# pwm_outputs.net
KiCad netlist of a schematic drawn in Altium Designer
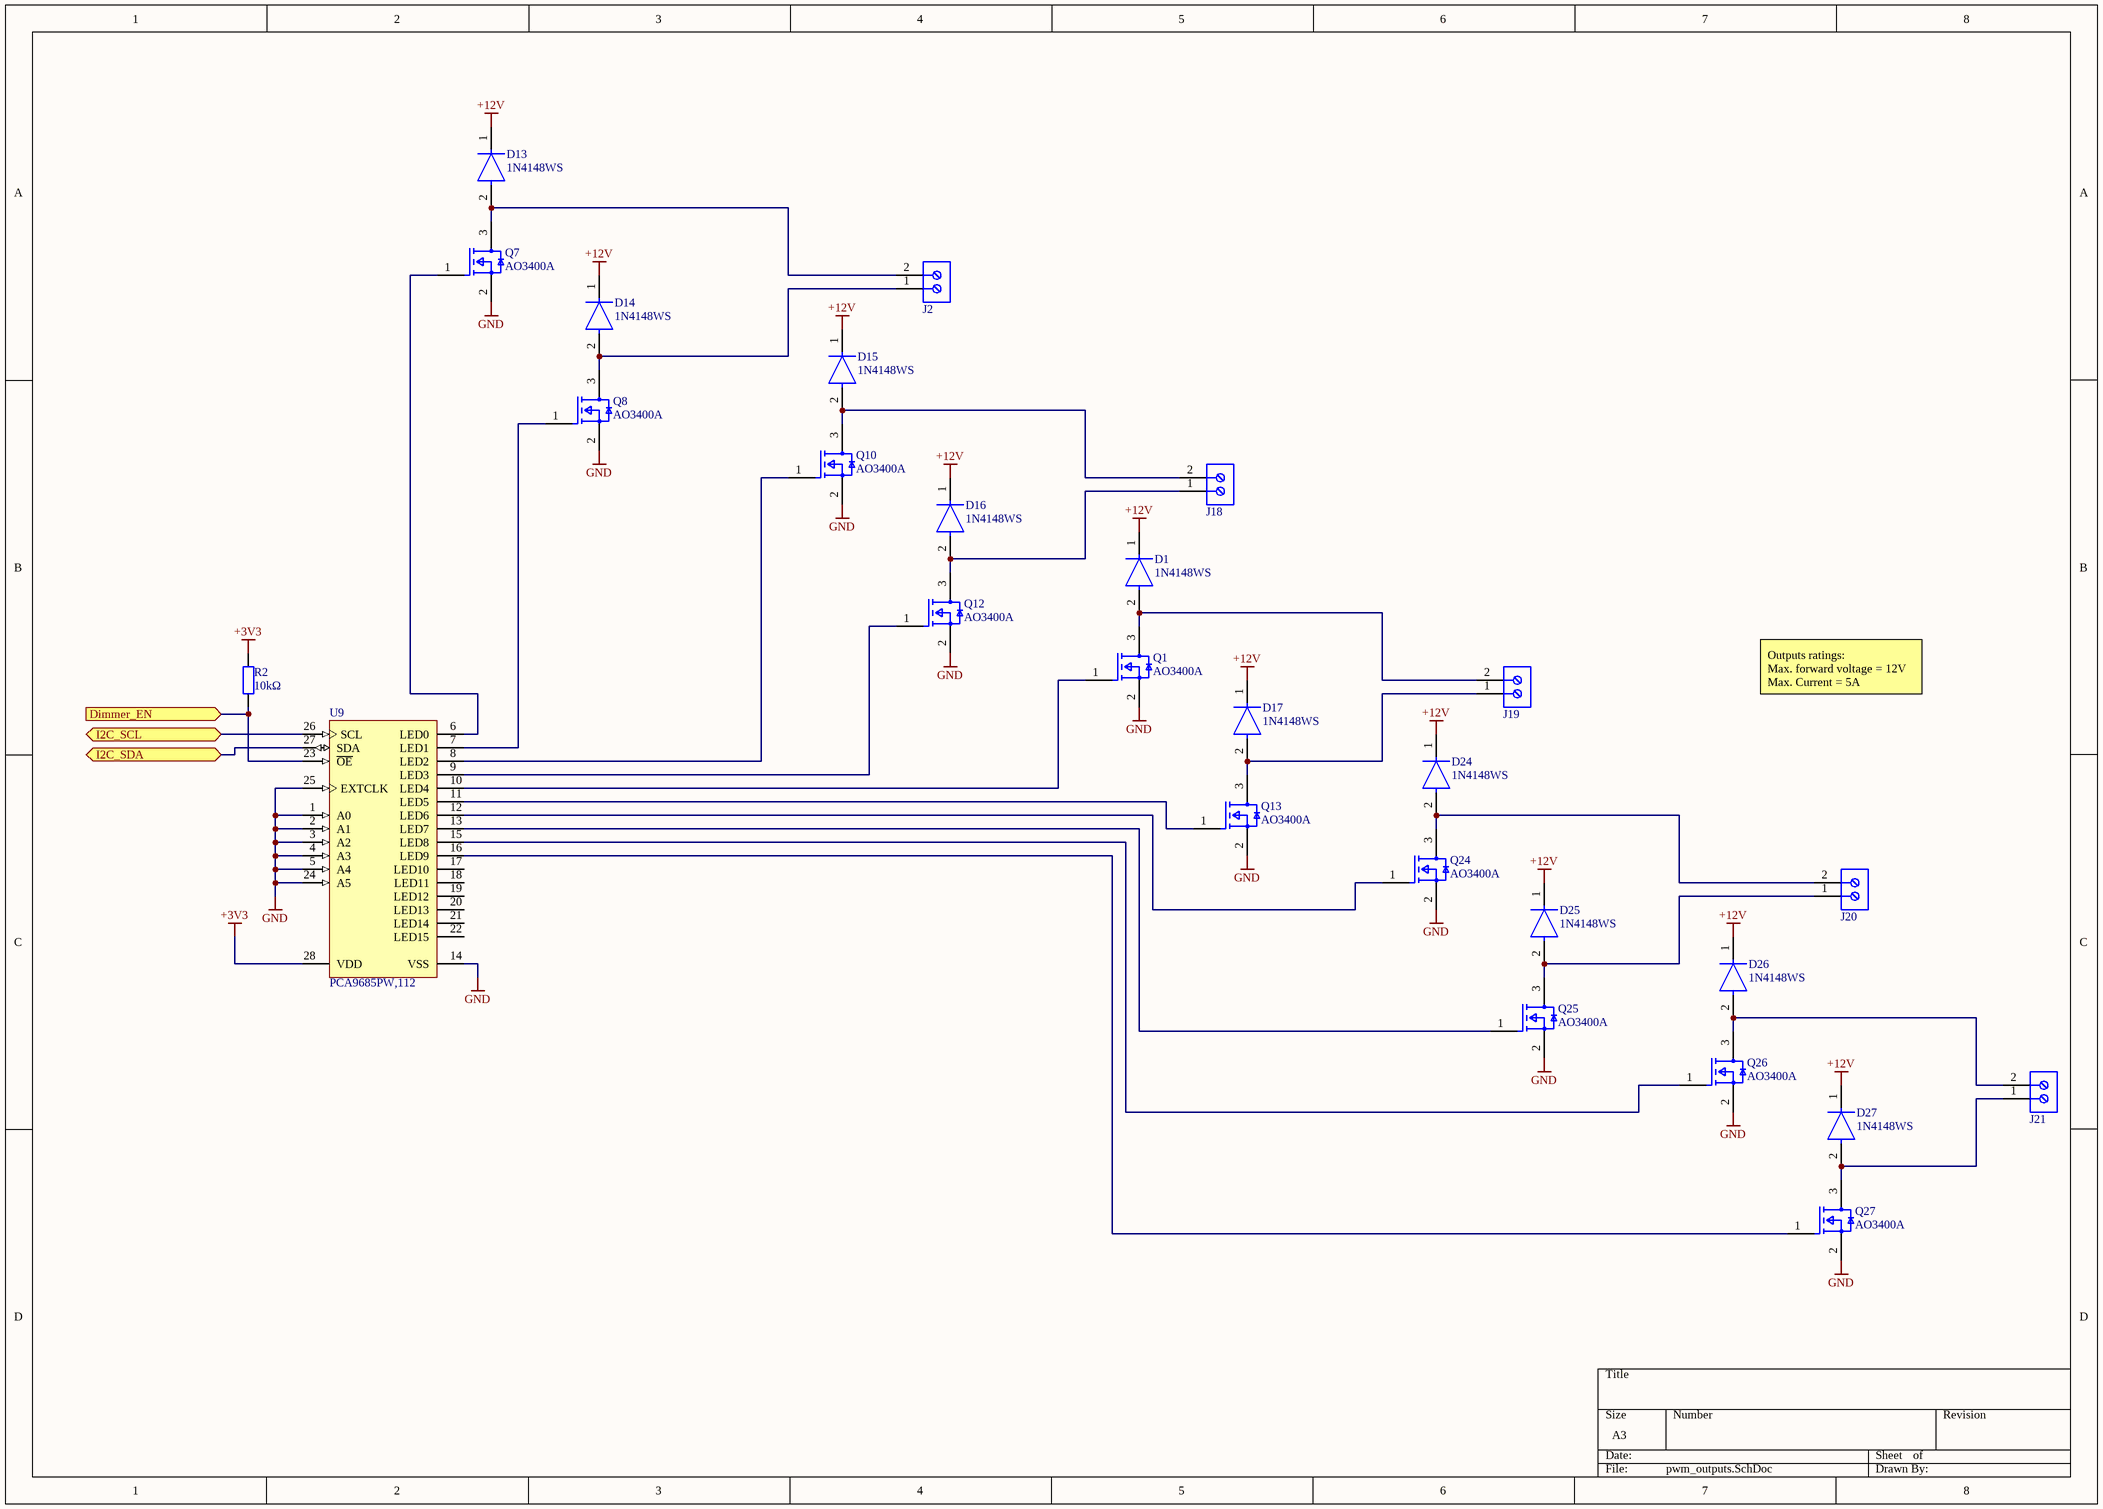
[diagram p0: pwm_outputs.SchDoc]

(export (version "E")
  (design (tool "Eeschema 10.0.6"))
  (components
    (comp (ref "D1")
      (value "1N4148WS")
      (footprint "FP-477AB-IPC_C")
      (description "DIODE GEN PURP 75V 150MA SOD323F")
      (libsource (lib "Altium Content Vault") (part "d7152d700b627762746794eb795d46e"))
    )
    (comp (ref "D13")
      (value "1N4148WS")
      (footprint "FP-477AB-IPC_C")
      (description "DIODE GEN PURP 75V 150MA SOD323F")
      (libsource (lib "Altium Content Vault") (part "d7152d700b627762746794eb795d46e"))
    )
    (comp (ref "D14")
      (value "1N4148WS")
      (footprint "FP-477AB-IPC_C")
      (description "DIODE GEN PURP 75V 150MA SOD323F")
      (libsource (lib "Altium Content Vault") (part "d7152d700b627762746794eb795d46e"))
    )
    (comp (ref "D15")
      (value "1N4148WS")
      (footprint "FP-477AB-IPC_C")
      (description "DIODE GEN PURP 75V 150MA SOD323F")
      (libsource (lib "Altium Content Vault") (part "d7152d700b627762746794eb795d46e"))
    )
    (comp (ref "D16")
      (value "1N4148WS")
      (footprint "FP-477AB-IPC_C")
      (description "DIODE GEN PURP 75V 150MA SOD323F")
      (libsource (lib "Altium Content Vault") (part "d7152d700b627762746794eb795d46e"))
    )
    (comp (ref "D17")
      (value "1N4148WS")
      (footprint "FP-477AB-IPC_C")
      (description "DIODE GEN PURP 75V 150MA SOD323F")
      (libsource (lib "Altium Content Vault") (part "d7152d700b627762746794eb795d46e"))
    )
    (comp (ref "D24")
      (value "1N4148WS")
      (footprint "FP-477AB-IPC_C")
      (description "DIODE GEN PURP 75V 150MA SOD323F")
      (libsource (lib "Altium Content Vault") (part "d7152d700b627762746794eb795d46e"))
    )
    (comp (ref "D25")
      (value "1N4148WS")
      (footprint "FP-477AB-IPC_C")
      (description "DIODE GEN PURP 75V 150MA SOD323F")
      (libsource (lib "Altium Content Vault") (part "d7152d700b627762746794eb795d46e"))
    )
    (comp (ref "D26")
      (value "1N4148WS")
      (footprint "FP-477AB-IPC_C")
      (description "DIODE GEN PURP 75V 150MA SOD323F")
      (libsource (lib "Altium Content Vault") (part "d7152d700b627762746794eb795d46e"))
    )
    (comp (ref "D27")
      (value "1N4148WS")
      (footprint "FP-477AB-IPC_C")
      (description "DIODE GEN PURP 75V 150MA SOD323F")
      (libsource (lib "Altium Content Vault") (part "d7152d700b627762746794eb795d46e"))
    )
    (comp (ref "J2")
      (value "282836-2")
      (footprint "TECO-282836-2_V")
      (description "Female Header, Pitch 5 mm, 1 x 2 Position, Height 10 mm, Tail Length 3.5 mm, Rohs, Bulk")
      (fields (field (name "VOLTAGE") "300V") (field (name "MANUFACTURER") "TE Connectivity"))
      (libsource (lib "Altium Content Vault") (part "CN-1P-F-TB2"))
    )
    (comp (ref "J18")
      (value "282836-2")
      (footprint "TECO-282836-2_V")
      (description "Female Header, Pitch 5 mm, 1 x 2 Position, Height 10 mm, Tail Length 3.5 mm, Rohs, Bulk")
      (fields (field (name "VOLTAGE") "300V") (field (name "MANUFACTURER") "TE Connectivity"))
      (libsource (lib "Altium Content Vault") (part "CN-1P-F-TB2"))
    )
    (comp (ref "J19")
      (value "282836-2")
      (footprint "TECO-282836-2_V")
      (description "Female Header, Pitch 5 mm, 1 x 2 Position, Height 10 mm, Tail Length 3.5 mm, Rohs, Bulk")
      (fields (field (name "VOLTAGE") "300V") (field (name "MANUFACTURER") "TE Connectivity"))
      (libsource (lib "Altium Content Vault") (part "CN-1P-F-TB2"))
    )
    (comp (ref "J20")
      (value "282836-2")
      (footprint "TECO-282836-2_V")
      (description "Female Header, Pitch 5 mm, 1 x 2 Position, Height 10 mm, Tail Length 3.5 mm, Rohs, Bulk")
      (fields (field (name "VOLTAGE") "300V") (field (name "MANUFACTURER") "TE Connectivity"))
      (libsource (lib "Altium Content Vault") (part "CN-1P-F-TB2"))
    )
    (comp (ref "J21")
      (value "282836-2")
      (footprint "TECO-282836-2_V")
      (description "Female Header, Pitch 5 mm, 1 x 2 Position, Height 10 mm, Tail Length 3.5 mm, Rohs, Bulk")
      (fields (field (name "VOLTAGE") "300V") (field (name "MANUFACTURER") "TE Connectivity"))
      (libsource (lib "Altium Content Vault") (part "CN-1P-F-TB2"))
    )
    (comp (ref "Q1")
      (value "AO3400A")
      (footprint "SOT-23")
      (description "MOSFET N-CH 30V 5.7A SOT23")
      (libsource (lib "integrated_library") (part "MOSFET_AO3400A"))
    )
    (comp (ref "Q7")
      (value "AO3400A")
      (footprint "SOT-23")
      (description "MOSFET N-CH 30V 5.7A SOT23")
      (libsource (lib "integrated_library") (part "MOSFET_AO3400A"))
    )
    (comp (ref "Q8")
      (value "AO3400A")
      (footprint "SOT-23")
      (description "MOSFET N-CH 30V 5.7A SOT23")
      (libsource (lib "integrated_library") (part "MOSFET_AO3400A"))
    )
    (comp (ref "Q10")
      (value "AO3400A")
      (footprint "SOT-23")
      (description "MOSFET N-CH 30V 5.7A SOT23")
      (libsource (lib "integrated_library") (part "MOSFET_AO3400A"))
    )
    (comp (ref "Q12")
      (value "AO3400A")
      (footprint "SOT-23")
      (description "MOSFET N-CH 30V 5.7A SOT23")
      (libsource (lib "integrated_library") (part "MOSFET_AO3400A"))
    )
    (comp (ref "Q13")
      (value "AO3400A")
      (footprint "SOT-23")
      (description "MOSFET N-CH 30V 5.7A SOT23")
      (libsource (lib "integrated_library") (part "MOSFET_AO3400A"))
    )
    (comp (ref "Q24")
      (value "AO3400A")
      (footprint "SOT-23")
      (description "MOSFET N-CH 30V 5.7A SOT23")
      (libsource (lib "integrated_library") (part "MOSFET_AO3400A"))
    )
    (comp (ref "Q25")
      (value "AO3400A")
      (footprint "SOT-23")
      (description "MOSFET N-CH 30V 5.7A SOT23")
      (libsource (lib "integrated_library") (part "MOSFET_AO3400A"))
    )
    (comp (ref "Q26")
      (value "AO3400A")
      (footprint "SOT-23")
      (description "MOSFET N-CH 30V 5.7A SOT23")
      (libsource (lib "integrated_library") (part "MOSFET_AO3400A"))
    )
    (comp (ref "Q27")
      (value "AO3400A")
      (footprint "SOT-23")
      (description "MOSFET N-CH 30V 5.7A SOT23")
      (libsource (lib "integrated_library") (part "MOSFET_AO3400A"))
    )
    (comp (ref "R2")
      (value "10kΩ")
      (footprint "RESC2013X50X30ML20T20")
      (description "Resistor")
      (libsource (lib "PCB_Project") (part "Res_0805"))
    )
    (comp (ref "U9")
      (value "PCA9685PW,112")
      (footprint "SOT361-1_V")
      (fields (field (name "PARTNUMBER") "PCA9685"))
      (libsource (lib "Altium Content Vault") (part "NXP-PCA9685-SOT361-1"))
    )
  )
  (nets
    (net (code "1") (name "+3V3") (class "Default")
      (node (ref "R2") (pin "2") (pinfunction "2_2") (pintype "passive"))
      (node (ref "U9") (pin "28") (pinfunction "VDD_28") (pintype "power_in"))
    )
    (net (code "2") (name "+12V") (class "Default")
      (node (ref "D1") (pin "1") (pinfunction "C_1") (pintype "passive"))
      (node (ref "D13") (pin "1") (pinfunction "C_1") (pintype "passive"))
      (node (ref "D14") (pin "1") (pinfunction "C_1") (pintype "passive"))
      (node (ref "D15") (pin "1") (pinfunction "C_1") (pintype "passive"))
      (node (ref "D16") (pin "1") (pinfunction "C_1") (pintype "passive"))
      (node (ref "D17") (pin "1") (pinfunction "C_1") (pintype "passive"))
      (node (ref "D24") (pin "1") (pinfunction "C_1") (pintype "passive"))
      (node (ref "D25") (pin "1") (pinfunction "C_1") (pintype "passive"))
      (node (ref "D26") (pin "1") (pinfunction "C_1") (pintype "passive"))
      (node (ref "D27") (pin "1") (pinfunction "C_1") (pintype "passive"))
    )
    (net (code "3") (name "/Dimmer_EN") (class "Default")
      (node (ref "R2") (pin "1") (pinfunction "1_1") (pintype "passive"))
      (node (ref "U9") (pin "23") (pinfunction "~{OE}_23") (pintype "input"))
    )
    (net (code "4") (name "/I2C_SCL") (class "Default")
      (node (ref "U9") (pin "26") (pinfunction "SCL_26") (pintype "input"))
    )
    (net (code "5") (name "/I2C_SDA") (class "Default")
      (node (ref "U9") (pin "27") (pinfunction "SDA_27") (pintype "bidirectional"))
    )
    (net (code "6") (name "GND") (class "Default")
      (node (ref "Q1") (pin "2") (pinfunction "S_2") (pintype "passive"))
      (node (ref "Q10") (pin "2") (pinfunction "S_2") (pintype "passive"))
      (node (ref "Q12") (pin "2") (pinfunction "S_2") (pintype "passive"))
      (node (ref "Q13") (pin "2") (pinfunction "S_2") (pintype "passive"))
      (node (ref "Q24") (pin "2") (pinfunction "S_2") (pintype "passive"))
      (node (ref "Q25") (pin "2") (pinfunction "S_2") (pintype "passive"))
      (node (ref "Q26") (pin "2") (pinfunction "S_2") (pintype "passive"))
      (node (ref "Q27") (pin "2") (pinfunction "S_2") (pintype "passive"))
      (node (ref "Q7") (pin "2") (pinfunction "S_2") (pintype "passive"))
      (node (ref "Q8") (pin "2") (pinfunction "S_2") (pintype "passive"))
      (node (ref "U9") (pin "1") (pinfunction "A0_1") (pintype "input"))
      (node (ref "U9") (pin "14") (pinfunction "VSS_14") (pintype "power_in"))
      (node (ref "U9") (pin "2") (pinfunction "A1_2") (pintype "input"))
      (node (ref "U9") (pin "24") (pinfunction "A5_24") (pintype "input"))
      (node (ref "U9") (pin "25") (pinfunction "EXTCLK_25") (pintype "input"))
      (node (ref "U9") (pin "3") (pinfunction "A2_3") (pintype "input"))
      (node (ref "U9") (pin "4") (pinfunction "A3_4") (pintype "input"))
      (node (ref "U9") (pin "5") (pinfunction "A4_5") (pintype "input"))
    )
    (net (code "7") (name "Net-(D1-A)") (class "Default")
      (node (ref "D1") (pin "2") (pinfunction "A_2") (pintype "passive"))
      (node (ref "J19") (pin "2") (pinfunction "2_2") (pintype "passive"))
      (node (ref "Q1") (pin "3") (pinfunction "D_3") (pintype "passive"))
    )
    (net (code "8") (name "Net-(D13-A)") (class "Default")
      (node (ref "D13") (pin "2") (pinfunction "A_2") (pintype "passive"))
      (node (ref "J2") (pin "2") (pinfunction "2_2") (pintype "passive"))
      (node (ref "Q7") (pin "3") (pinfunction "D_3") (pintype "passive"))
    )
    (net (code "9") (name "Net-(D14-A)") (class "Default")
      (node (ref "D14") (pin "2") (pinfunction "A_2") (pintype "passive"))
      (node (ref "J2") (pin "1") (pinfunction "1_1") (pintype "passive"))
      (node (ref "Q8") (pin "3") (pinfunction "D_3") (pintype "passive"))
    )
    (net (code "10") (name "Net-(D15-A)") (class "Default")
      (node (ref "D15") (pin "2") (pinfunction "A_2") (pintype "passive"))
      (node (ref "J18") (pin "2") (pinfunction "2_2") (pintype "passive"))
      (node (ref "Q10") (pin "3") (pinfunction "D_3") (pintype "passive"))
    )
    (net (code "11") (name "Net-(D16-A)") (class "Default")
      (node (ref "D16") (pin "2") (pinfunction "A_2") (pintype "passive"))
      (node (ref "J18") (pin "1") (pinfunction "1_1") (pintype "passive"))
      (node (ref "Q12") (pin "3") (pinfunction "D_3") (pintype "passive"))
    )
    (net (code "12") (name "Net-(D17-A)") (class "Default")
      (node (ref "D17") (pin "2") (pinfunction "A_2") (pintype "passive"))
      (node (ref "J19") (pin "1") (pinfunction "1_1") (pintype "passive"))
      (node (ref "Q13") (pin "3") (pinfunction "D_3") (pintype "passive"))
    )
    (net (code "13") (name "Net-(D24-A)") (class "Default")
      (node (ref "D24") (pin "2") (pinfunction "A_2") (pintype "passive"))
      (node (ref "J20") (pin "2") (pinfunction "2_2") (pintype "passive"))
      (node (ref "Q24") (pin "3") (pinfunction "D_3") (pintype "passive"))
    )
    (net (code "14") (name "Net-(D25-A)") (class "Default")
      (node (ref "D25") (pin "2") (pinfunction "A_2") (pintype "passive"))
      (node (ref "J20") (pin "1") (pinfunction "1_1") (pintype "passive"))
      (node (ref "Q25") (pin "3") (pinfunction "D_3") (pintype "passive"))
    )
    (net (code "15") (name "Net-(D26-A)") (class "Default")
      (node (ref "D26") (pin "2") (pinfunction "A_2") (pintype "passive"))
      (node (ref "J21") (pin "2") (pinfunction "2_2") (pintype "passive"))
      (node (ref "Q26") (pin "3") (pinfunction "D_3") (pintype "passive"))
    )
    (net (code "16") (name "Net-(D27-A)") (class "Default")
      (node (ref "D27") (pin "2") (pinfunction "A_2") (pintype "passive"))
      (node (ref "J21") (pin "1") (pinfunction "1_1") (pintype "passive"))
      (node (ref "Q27") (pin "3") (pinfunction "D_3") (pintype "passive"))
    )
    (net (code "17") (name "Net-(Q1-G)") (class "Default")
      (node (ref "Q1") (pin "1") (pinfunction "G_1") (pintype "passive"))
      (node (ref "U9") (pin "10") (pinfunction "LED4_10") (pintype "tri_state"))
    )
    (net (code "18") (name "Net-(Q7-G)") (class "Default")
      (node (ref "Q7") (pin "1") (pinfunction "G_1") (pintype "passive"))
      (node (ref "U9") (pin "6") (pinfunction "LED0_6") (pintype "tri_state"))
    )
    (net (code "19") (name "Net-(Q8-G)") (class "Default")
      (node (ref "Q8") (pin "1") (pinfunction "G_1") (pintype "passive"))
      (node (ref "U9") (pin "7") (pinfunction "LED1_7") (pintype "tri_state"))
    )
    (net (code "20") (name "Net-(Q10-G)") (class "Default")
      (node (ref "Q10") (pin "1") (pinfunction "G_1") (pintype "passive"))
      (node (ref "U9") (pin "8") (pinfunction "LED2_8") (pintype "tri_state"))
    )
    (net (code "21") (name "Net-(Q12-G)") (class "Default")
      (node (ref "Q12") (pin "1") (pinfunction "G_1") (pintype "passive"))
      (node (ref "U9") (pin "9") (pinfunction "LED3_9") (pintype "tri_state"))
    )
    (net (code "22") (name "Net-(Q13-G)") (class "Default")
      (node (ref "Q13") (pin "1") (pinfunction "G_1") (pintype "passive"))
      (node (ref "U9") (pin "11") (pinfunction "LED5_11") (pintype "tri_state"))
    )
    (net (code "23") (name "Net-(Q24-G)") (class "Default")
      (node (ref "Q24") (pin "1") (pinfunction "G_1") (pintype "passive"))
      (node (ref "U9") (pin "12") (pinfunction "LED6_12") (pintype "tri_state"))
    )
    (net (code "24") (name "Net-(Q25-G)") (class "Default")
      (node (ref "Q25") (pin "1") (pinfunction "G_1") (pintype "passive"))
      (node (ref "U9") (pin "13") (pinfunction "LED7_13") (pintype "tri_state"))
    )
    (net (code "25") (name "Net-(Q26-G)") (class "Default")
      (node (ref "Q26") (pin "1") (pinfunction "G_1") (pintype "passive"))
      (node (ref "U9") (pin "15") (pinfunction "LED8_15") (pintype "tri_state"))
    )
    (net (code "26") (name "Net-(Q27-G)") (class "Default")
      (node (ref "Q27") (pin "1") (pinfunction "G_1") (pintype "passive"))
      (node (ref "U9") (pin "16") (pinfunction "LED9_16") (pintype "tri_state"))
    )
    (net (code "27") (name "unconnected-(U9-LED10-Pad17)") (class "Default")
      (node (ref "U9") (pin "17") (pinfunction "LED10_17") (pintype "tri_state"))
    )
    (net (code "28") (name "unconnected-(U9-LED11-Pad18)") (class "Default")
      (node (ref "U9") (pin "18") (pinfunction "LED11_18") (pintype "tri_state"))
    )
    (net (code "29") (name "unconnected-(U9-LED12-Pad19)") (class "Default")
      (node (ref "U9") (pin "19") (pinfunction "LED12_19") (pintype "tri_state"))
    )
    (net (code "30") (name "unconnected-(U9-LED13-Pad20)") (class "Default")
      (node (ref "U9") (pin "20") (pinfunction "LED13_20") (pintype "tri_state"))
    )
    (net (code "31") (name "unconnected-(U9-LED14-Pad21)") (class "Default")
      (node (ref "U9") (pin "21") (pinfunction "LED14_21") (pintype "tri_state"))
    )
    (net (code "32") (name "unconnected-(U9-LED15-Pad22)") (class "Default")
      (node (ref "U9") (pin "22") (pinfunction "LED15_22") (pintype "tri_state"))
    )
  )
)
